# STM32F103RCT6_V2_1.net
KiCad netlist of a schematic drawn in Altium Designer
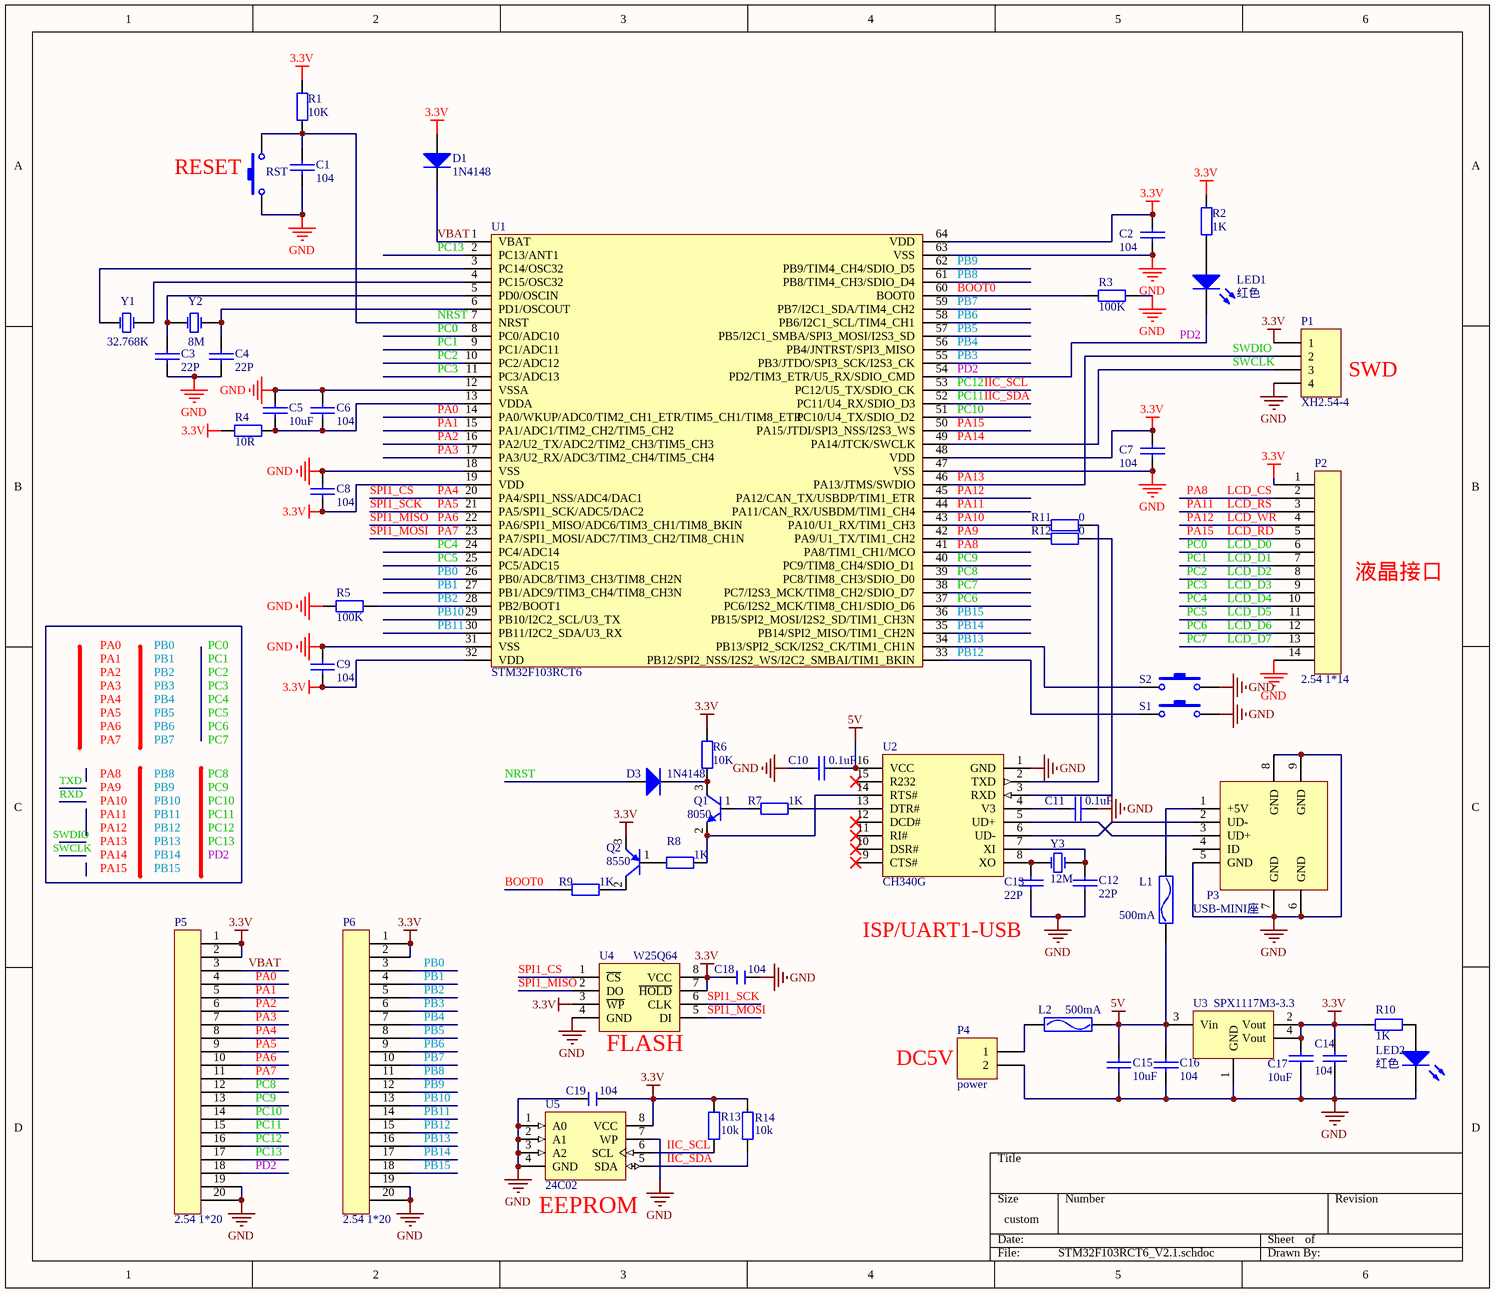
[diagram p0: STM32F103RCT6_V2.1.schdoc]

(export (version "E")
  (design (tool "Eeschema 10.0.6"))
  (components
    (comp (ref "C1") (value "104") (footprint "0805") (libsource (lib "Sch_Device__2010") (part "贴片电容 0805")))
    (comp (ref "C2") (value "104") (footprint "0805") (libsource (lib "Sch_Device__2010") (part "贴片电容 0805")))
    (comp (ref "C3") (value "22P") (footprint "0805") (libsource (lib "Sch_Device__2010") (part "贴片电容 0805")))
    (comp (ref "C4") (value "22P") (footprint "0805") (libsource (lib "Sch_Device__2010") (part "贴片电容 0805")))
    (comp (ref "C5")
      (value "10uF")
      (footprint "1206")
      (libsource (lib "Sch_Device__2010") (part "贴片电容 0805"))
    )
    (comp (ref "C6") (value "104") (footprint "0805") (libsource (lib "Sch_Device__2010") (part "贴片电容 0805")))
    (comp (ref "C7") (value "104") (footprint "0805") (libsource (lib "Sch_Device__2010") (part "贴片电容 0805")))
    (comp (ref "C8") (value "104") (footprint "0805") (libsource (lib "Sch_Device__2010") (part "贴片电容 0805")))
    (comp (ref "C9") (value "104") (footprint "0805") (libsource (lib "Sch_Device__2010") (part "贴片电容 0805")))
    (comp (ref "C10")
      (value "0.1uF")
      (footprint "0805")
      (libsource (lib "Sch_Device__2010") (part "贴片电容 0805"))
    )
    (comp (ref "C11")
      (value "0.1uF")
      (footprint "0805")
      (libsource (lib "Sch_Device__2010") (part "贴片电容 0805"))
    )
    (comp (ref "C12")
      (value "22P")
      (footprint "0805")
      (libsource (lib "Sch_Device__2010") (part "贴片电容 0805"))
    )
    (comp (ref "C13")
      (value "22P")
      (footprint "0805")
      (libsource (lib "Sch_Device__2010") (part "贴片电容 0805"))
    )
    (comp (ref "C14")
      (value "104")
      (footprint "0805")
      (libsource (lib "Sch_Device_Simple") (part "贴片电容 0805"))
    )
    (comp (ref "C15")
      (value "10uF")
      (footprint "1206")
      (libsource (lib "Sch_Device_Simple") (part "贴片电容 0805"))
    )
    (comp (ref "C16")
      (value "104")
      (footprint "0805")
      (libsource (lib "Sch_Device_Simple") (part "贴片电容 0805"))
    )
    (comp (ref "C17")
      (value "10uF")
      (footprint "1206")
      (libsource (lib "Sch_Device_Simple") (part "贴片电容 0805"))
    )
    (comp (ref "C18")
      (value "104")
      (footprint "0805")
      (description "无极性贴片电容")
      (fields (field (name "版权归属") "源创客"))
      (libsource (lib "STM32F407_CORE_BOARD") (part "C"))
    )
    (comp (ref "C19")
      (value "104")
      (footprint "0805")
      (description "无极性贴片电容")
      (fields (field (name "版权归属") "源创客"))
      (libsource (lib "STM32F407_CORE_BOARD") (part "C"))
    )
    (comp (ref "D1")
      (value "1N4148")
      (footprint "二极管 贴片 IN4148")
      (libsource (lib "Sch_Device_veryaz") (part "二极管 贴片 1N4148"))
    )
    (comp (ref "D3")
      (value "1N4148")
      (footprint "二极管 贴片 IN4148")
      (libsource (lib "") (part "二极管 贴片 1N4148_1"))
    )
    (comp (ref "L1") (value "500mA") (footprint "0805") (libsource (lib "Sch_Device_veryaz") (part "保险_自恢复")))
    (comp (ref "L2") (value "500mA") (footprint "0805") (libsource (lib "Sch_Device_veryaz") (part "保险_自恢复")))
    (comp (ref "LED1")
      (value "红色")
      (footprint "LED0805")
      (description "D_RED_D")
      (libsource (lib "Sch_Device_Simple") (part "发光二极管 Φ3"))
    )
    (comp (ref "LED2")
      (value "红色")
      (footprint "LED0805")
      (description "D_RED_D")
      (libsource (lib "Sch_Device_Simple") (part "发光二极管 Φ3"))
    )
    (comp (ref "P1")
      (value "XH2.54-4")
      (footprint "VH2.54_4")
      (libsource (lib "Sch_Device_veryaz") (part "联结件 XH2.54-4"))
    )
    (comp (ref "P2")
      (value "2.54 1*14")
      (footprint "单排插针 2.54 1*14")
      (libsource (lib "Sch_Device_veryaz") (part "联结件 单排插针 2.54 1*14"))
    )
    (comp (ref "P3")
      (value "USB-MINI座")
      (footprint "USB MINI DIP")
      (libsource (lib "Sch_Device_veryaz") (part "联结件 USB-MINI座"))
    )
    (comp (ref "P4")
      (value "power")
      (footprint "VH2.54_2")
      (libsource (lib "Sch_Device_Simple") (part "联结件 电源插头座"))
    )
    (comp (ref "P5")
      (value "2.54 1*20")
      (footprint "单排插针 2.54 1*20")
      (libsource (lib "Sch_Device_veryaz") (part "联结件 单排插针 2.54 1*20"))
    )
    (comp (ref "P6")
      (value "2.54 1*20")
      (footprint "单排插针 2.54 1*20")
      (libsource (lib "Sch_Device_veryaz") (part "联结件 单排插针 2.54 1*20"))
    )
    (comp (ref "Q1")
      (value "8050")
      (footprint "sot23b")
      (description "NPN 8050")
      (libsource (lib "Sch_Device_veryaz") (part "三极管 贴片 NPN"))
    )
    (comp (ref "Q2")
      (value "8550")
      (footprint "sot23b")
      (description "PNP 8550")
      (libsource (lib "Sch_Device_veryaz") (part "三极管 贴片PNP"))
    )
    (comp (ref "R1") (value "10K") (footprint "0805") (libsource (lib "") (part "贴片电阻 0603_2")))
    (comp (ref "R2") (value "1K") (footprint "0805") (libsource (lib "") (part "贴片电阻 0805_2")))
    (comp (ref "R3")
      (value "100K")
      (footprint "0805")
      (libsource (lib "Sch_Device_Simple") (part "贴片电阻 0805"))
    )
    (comp (ref "R4")
      (value "10R")
      (footprint "0805")
      (libsource (lib "Sch_Device_veryaz") (part "贴片电阻 0603"))
    )
    (comp (ref "R5") (value "100K") (footprint "0805") (libsource (lib "") (part "贴片电阻 0805_1")))
    (comp (ref "R6") (value "10K") (footprint "0805") (libsource (lib "") (part "贴片电阻 0603_1")))
    (comp (ref "R7") (value "1K") (footprint "0805") (libsource (lib "Sch_Device_veryaz") (part "贴片电阻 0603")))
    (comp (ref "R8") (value "1K") (footprint "0805") (libsource (lib "Sch_Device_veryaz") (part "贴片电阻 0603")))
    (comp (ref "R9") (value "1K") (footprint "0805") (libsource (lib "Sch_Device_veryaz") (part "贴片电阻 0603")))
    (comp (ref "R10")
      (value "1K")
      (footprint "0805")
      (libsource (lib "Sch_Device_Simple") (part "贴片电阻 0805"))
    )
    (comp (ref "R11") (value "0") (footprint "0805") (libsource (lib "Sch_Device_Simple") (part "贴片电阻 0805")))
    (comp (ref "R12") (value "0") (footprint "0805") (libsource (lib "Sch_Device_Simple") (part "贴片电阻 0805")))
    (comp (ref "R13")
      (value "10k")
      (footprint "0805")
      (description "贴片电阻")
      (fields (field (name "版权归属") "源创客"))
      (libsource (lib "STM32F407_CORE_BOARD") (part "R"))
    )
    (comp (ref "R14")
      (value "10k")
      (footprint "0805")
      (description "贴片电阻")
      (fields (field (name "版权归属") "源创客"))
      (libsource (lib "STM32F407_CORE_BOARD") (part "R"))
    )
    (comp (ref "RST") (value "key") (footprint "按键 轻触  6*3") (libsource (lib "") (part "按键 轻触 3*6_1")))
    (comp (ref "S1")
      (value "key")
      (footprint "按键 轻触  6*3")
      (libsource (lib "Sch_Device_veryaz") (part "按键 轻触 3*6"))
    )
    (comp (ref "S2")
      (value "key")
      (footprint "按键 轻触  6*3")
      (libsource (lib "Sch_Device_veryaz") (part "按键 轻触 3*6"))
    )
    (comp (ref "U1")
      (value "STM32F103RCT6")
      (footprint "Pcb Device_veryaz:LQFP64")
      (libsource (lib "Sch_Device_veryaz") (part "贴片芯片 STM32F103RCT6"))
    )
    (comp (ref "U2")
      (value "CH340G")
      (footprint "SOIC16")
      (libsource (lib "Sch_Device_veryaz") (part "贴片芯片 CH340G"))
    )
    (comp (ref "U3")
      (value "SPX1117M3-3.3")
      (footprint "SOT223")
      (libsource (lib "Sch_Device_veryaz") (part "贴片芯片 SPX1117M3-5.0"))
    )
    (comp (ref "U4")
      (value "W25Q64")
      (footprint "SO8-W")
      (description "外置Flash")
      (fields (field (name "版权归属") "源创客"))
      (libsource (lib "STM32F407_CORE_BOARD") (part "W25Qxx"))
    )
    (comp (ref "U5")
      (value "24C02")
      (footprint "SOIC8")
      (description "外置EEPROM")
      (fields (field (name "版权归属") "源创客"))
      (libsource (lib "STM32F407_CORE_BOARD") (part "24Cxx"))
    )
    (comp (ref "Y1")
      (value "32.768K")
      (footprint "晶振 卧 BCY-W2/D3.1")
      (libsource (lib "Sch_Device_veryaz") (part "晶振 直插矮"))
    )
    (comp (ref "Y2")
      (value "8M")
      (footprint "晶振 BCY-W2/E4.7")
      (libsource (lib "Sch_Device_veryaz") (part "晶振 直插矮"))
    )
    (comp (ref "Y3")
      (value "12M")
      (footprint "晶振 BCY-W2/E4.7")
      (libsource (lib "Sch_Device_veryaz") (part "晶振 直插矮"))
    )
  )
  (nets
    (net (code "1") (name "/BOOT0") (class "Default")
      (node (ref "R3") (pin "2") (pinfunction "2_2") (pintype "passive"))
      (node (ref "R9") (pin "1") (pinfunction "1_1") (pintype "passive"))
      (node (ref "U1") (pin "60") (pinfunction "BOOT0_60") (pintype "passive"))
    )
    (net (code "2") (name "/IIC_SCL") (class "Default")
      (node (ref "P5") (pin "16") (pinfunction "16_16") (pintype "passive"))
      (node (ref "R13") (pin "2") (pinfunction "2_2") (pintype "passive"))
      (node (ref "U1") (pin "53") (pinfunction "PC12/U5_TX/SDIO_CK_53") (pintype "passive"))
      (node (ref "U5") (pin "6") (pinfunction "SCL_6") (pintype "input"))
    )
    (net (code "3") (name "/IIC_SDA") (class "Default")
      (node (ref "P5") (pin "15") (pinfunction "15_15") (pintype "passive"))
      (node (ref "R14") (pin "2") (pinfunction "2_2") (pintype "passive"))
      (node (ref "U1") (pin "52") (pinfunction "PC11/U4_RX/SDIO_D3_52") (pintype "passive"))
      (node (ref "U5") (pin "5") (pinfunction "SDA_5") (pintype "bidirectional"))
    )
    (net (code "4") (name "/LCD_CS") (class "Default")
      (node (ref "P2") (pin "2") (pinfunction "2_2") (pintype "passive"))
      (node (ref "U1") (pin "41") (pinfunction "PA8/TIM1_CH1/MCO_41") (pintype "passive"))
    )
    (net (code "5") (name "/LCD_D0") (class "Default")
      (node (ref "P2") (pin "6") (pinfunction "6_6") (pintype "passive"))
      (node (ref "U1") (pin "8") (pinfunction "PC0/ADC10_8") (pintype "passive"))
    )
    (net (code "6") (name "/LCD_D1") (class "Default")
      (node (ref "P2") (pin "7") (pinfunction "7_7") (pintype "passive"))
      (node (ref "U1") (pin "9") (pinfunction "PC1/ADC11_9") (pintype "passive"))
    )
    (net (code "7") (name "/LCD_D2") (class "Default")
      (node (ref "P2") (pin "8") (pinfunction "8_8") (pintype "passive"))
      (node (ref "U1") (pin "10") (pinfunction "PC2/ADC12_10") (pintype "passive"))
    )
    (net (code "8") (name "/LCD_D3") (class "Default")
      (node (ref "P2") (pin "9") (pinfunction "9_9") (pintype "passive"))
      (node (ref "U1") (pin "11") (pinfunction "PC3/ADC13_11") (pintype "passive"))
    )
    (net (code "9") (name "/LCD_D4") (class "Default")
      (node (ref "P2") (pin "10") (pinfunction "10_10") (pintype "passive"))
      (node (ref "U1") (pin "24") (pinfunction "PC4/ADC14_24") (pintype "passive"))
    )
    (net (code "10") (name "/LCD_D5") (class "Default")
      (node (ref "P2") (pin "11") (pinfunction "11_11") (pintype "passive"))
      (node (ref "U1") (pin "25") (pinfunction "PC5/ADC15_25") (pintype "passive"))
    )
    (net (code "11") (name "/LCD_D6") (class "Default")
      (node (ref "P2") (pin "12") (pinfunction "12_12") (pintype "passive"))
      (node (ref "U1") (pin "37") (pinfunction "PC6/I2S2_MCK/TIM8_CH1/SDIO_D6_37") (pintype "passive"))
    )
    (net (code "12") (name "/LCD_D7") (class "Default")
      (node (ref "P2") (pin "13") (pinfunction "13_13") (pintype "passive"))
      (node (ref "U1") (pin "38") (pinfunction "PC7/I2S3_MCK/TIM8_CH2/SDIO_D7_38") (pintype "passive"))
    )
    (net (code "13") (name "/LCD_RD") (class "Default")
      (node (ref "P2") (pin "5") (pinfunction "5_5") (pintype "passive"))
      (node (ref "U1") (pin "50") (pinfunction "PA15/JTDI/SPI3_NSS/I2S3_WS_50") (pintype "passive"))
    )
    (net (code "14") (name "/LCD_RS") (class "Default")
      (node (ref "P2") (pin "3") (pinfunction "3_3") (pintype "passive"))
      (node (ref "U1") (pin "44") (pinfunction "PA11/CAN_RX/USBDM/TIM1_CH4_44") (pintype "passive"))
    )
    (net (code "15") (name "/LCD_WR") (class "Default")
      (node (ref "P2") (pin "4") (pinfunction "4_4") (pintype "passive"))
      (node (ref "U1") (pin "45") (pinfunction "PA12/CAN_TX/USBDP/TIM1_ETR_45") (pintype "passive"))
    )
    (net (code "16") (name "/NRST") (class "Default")
      (node (ref "C1") (pin "2") (pintype "passive"))
      (node (ref "D3") (pin "1") (pinfunction "A_1") (pintype "passive"))
      (node (ref "R1") (pin "2") (pinfunction "2_2") (pintype "passive"))
      (node (ref "RST") (pin "2") (pinfunction "2_2") (pintype "passive"))
      (node (ref "U1") (pin "7") (pinfunction "NRST_7") (pintype "passive"))
    )
    (net (code "17") (name "/PA0") (class "Default")
      (node (ref "P5") (pin "4") (pinfunction "4_4") (pintype "passive"))
      (node (ref "U1") (pin "14") (pinfunction "PA0/WKUP/ADC0/TIM2_CH1_ETR/TIM5_CH1/TIM8_ETR_14") (pintype "passive"))
    )
    (net (code "18") (name "/PA1") (class "Default")
      (node (ref "P5") (pin "5") (pinfunction "5_5") (pintype "passive"))
      (node (ref "U1") (pin "15") (pinfunction "PA1/ADC1/TIM2_CH2/TIM5_CH2_15") (pintype "passive"))
    )
    (net (code "19") (name "/PA2") (class "Default")
      (node (ref "P5") (pin "6") (pinfunction "6_6") (pintype "passive"))
      (node (ref "U1") (pin "16") (pinfunction "PA2/U2_TX/ADC2/TIM2_CH3/TIM5_CH3_16") (pintype "passive"))
    )
    (net (code "20") (name "/PA3") (class "Default")
      (node (ref "P5") (pin "7") (pinfunction "7_7") (pintype "passive"))
      (node (ref "U1") (pin "17") (pinfunction "PA3/U2_RX/ADC3/TIM2_CH4/TIM5_CH4_17") (pintype "passive"))
    )
    (net (code "21") (name "/PA4") (class "Default")
      (node (ref "P5") (pin "8") (pinfunction "8_8") (pintype "passive"))
      (node (ref "U1") (pin "20") (pinfunction "PA4/SPI1_NSS/ADC4/DAC1_20") (pintype "passive"))
      (node (ref "U4") (pin "1") (pinfunction "~{CS}_1") (pintype "passive"))
    )
    (net (code "22") (name "/PA5") (class "Default")
      (node (ref "P5") (pin "9") (pinfunction "9_9") (pintype "passive"))
      (node (ref "U1") (pin "21") (pinfunction "PA5/SPI1_SCK/ADC5/DAC2_21") (pintype "passive"))
      (node (ref "U4") (pin "6") (pinfunction "CLK_6") (pintype "passive"))
    )
    (net (code "23") (name "/PA6") (class "Default")
      (node (ref "P5") (pin "10") (pinfunction "10_10") (pintype "passive"))
      (node (ref "U1") (pin "22") (pinfunction "PA6/SPI1_MISO/ADC6/TIM3_CH1/TIM8_BKIN_22") (pintype "passive"))
      (node (ref "U4") (pin "2") (pinfunction "DO_2") (pintype "passive"))
    )
    (net (code "24") (name "/PA7") (class "Default")
      (node (ref "P5") (pin "11") (pinfunction "11_11") (pintype "passive"))
      (node (ref "U1") (pin "23") (pinfunction "PA7/SPI1_MOSI/ADC7/TIM3_CH2/TIM8_CH1N_23") (pintype "passive"))
      (node (ref "U4") (pin "5") (pinfunction "DI_5") (pintype "passive"))
    )
    (net (code "25") (name "/PA9") (class "Default")
      (node (ref "R12") (pin "2") (pinfunction "2_2") (pintype "passive"))
      (node (ref "U1") (pin "42") (pinfunction "PA9/U1_TX/TIM1_CH2_42") (pintype "passive"))
    )
    (net (code "26") (name "/PA10") (class "Default")
      (node (ref "R11") (pin "2") (pinfunction "2_2") (pintype "passive"))
      (node (ref "U1") (pin "43") (pinfunction "PA10/U1_RX/TIM1_CH3_43") (pintype "passive"))
    )
    (net (code "27") (name "/PA13") (class "Default")
      (node (ref "P1") (pin "2") (pinfunction "2_2") (pintype "passive"))
      (node (ref "U1") (pin "46") (pinfunction "PA13/JTMS/SWDIO_46") (pintype "passive"))
    )
    (net (code "28") (name "/PA14") (class "Default")
      (node (ref "P1") (pin "3") (pinfunction "3_3") (pintype "passive"))
      (node (ref "U1") (pin "49") (pinfunction "PA14/JTCK/SWCLK_49") (pintype "passive"))
    )
    (net (code "29") (name "/PB0") (class "Default")
      (node (ref "P6") (pin "3") (pinfunction "3_3") (pintype "passive"))
      (node (ref "U1") (pin "26") (pinfunction "PB0/ADC8/TIM3_CH3/TIM8_CH2N_26") (pintype "passive"))
    )
    (net (code "30") (name "/PB1") (class "Default")
      (node (ref "P6") (pin "4") (pinfunction "4_4") (pintype "passive"))
      (node (ref "U1") (pin "27") (pinfunction "PB1/ADC9/TIM3_CH4/TIM8_CH3N_27") (pintype "passive"))
    )
    (net (code "31") (name "/PB2") (class "Default")
      (node (ref "P6") (pin "5") (pinfunction "5_5") (pintype "passive"))
      (node (ref "R5") (pin "2") (pinfunction "2_2") (pintype "passive"))
      (node (ref "U1") (pin "28") (pinfunction "PB2/BOOT1_28") (pintype "passive"))
    )
    (net (code "32") (name "/PB3") (class "Default")
      (node (ref "P6") (pin "6") (pinfunction "6_6") (pintype "passive"))
      (node (ref "U1") (pin "55") (pinfunction "PB3/JTDO/SPI3_SCK/I2S3_CK_55") (pintype "passive"))
    )
    (net (code "33") (name "/PB4") (class "Default")
      (node (ref "P6") (pin "7") (pinfunction "7_7") (pintype "passive"))
      (node (ref "U1") (pin "56") (pinfunction "PB4/JNTRST/SPI3_MISO_56") (pintype "passive"))
    )
    (net (code "34") (name "/PB5") (class "Default")
      (node (ref "P6") (pin "8") (pinfunction "8_8") (pintype "passive"))
      (node (ref "U1") (pin "57") (pinfunction "PB5/I2C1_SMBA/SPI3_MOSI/I2S3_SD_57") (pintype "passive"))
    )
    (net (code "35") (name "/PB6") (class "Default")
      (node (ref "P6") (pin "9") (pinfunction "9_9") (pintype "passive"))
      (node (ref "U1") (pin "58") (pinfunction "PB6/I2C1_SCL/TIM4_CH1_58") (pintype "passive"))
    )
    (net (code "36") (name "/PB7") (class "Default")
      (node (ref "P6") (pin "10") (pinfunction "10_10") (pintype "passive"))
      (node (ref "U1") (pin "59") (pinfunction "PB7/I2C1_SDA/TIM4_CH2_59") (pintype "passive"))
    )
    (net (code "37") (name "/PB8") (class "Default")
      (node (ref "P6") (pin "11") (pinfunction "11_11") (pintype "passive"))
      (node (ref "U1") (pin "61") (pinfunction "PB8/TIM4_CH3/SDIO_D4_61") (pintype "passive"))
    )
    (net (code "38") (name "/PB9") (class "Default")
      (node (ref "P6") (pin "12") (pinfunction "12_12") (pintype "passive"))
      (node (ref "U1") (pin "62") (pinfunction "PB9/TIM4_CH4/SDIO_D5_62") (pintype "passive"))
    )
    (net (code "39") (name "/PB10") (class "Default")
      (node (ref "P6") (pin "13") (pinfunction "13_13") (pintype "passive"))
      (node (ref "U1") (pin "29") (pinfunction "PB10/I2C2_SCL/U3_TX_29") (pintype "passive"))
    )
    (net (code "40") (name "/PB11") (class "Default")
      (node (ref "P6") (pin "14") (pinfunction "14_14") (pintype "passive"))
      (node (ref "U1") (pin "30") (pinfunction "PB11/I2C2_SDA/U3_RX_30") (pintype "passive"))
    )
    (net (code "41") (name "/PB12") (class "Default")
      (node (ref "P6") (pin "15") (pinfunction "15_15") (pintype "passive"))
      (node (ref "S1") (pin "2") (pinfunction "2_2") (pintype "passive"))
      (node (ref "U1") (pin "33") (pinfunction "PB12/SPI2_NSS/I2S2_WS/I2C2_SMBAI/TIM1_BKIN_33") (pintype "passive"))
    )
    (net (code "42") (name "/PB13") (class "Default")
      (node (ref "P6") (pin "16") (pinfunction "16_16") (pintype "passive"))
      (node (ref "S2") (pin "2") (pinfunction "2_2") (pintype "passive"))
      (node (ref "U1") (pin "34") (pinfunction "PB13/SPI2_SCK/I2S2_CK/TIM1_CH1N_34") (pintype "passive"))
    )
    (net (code "43") (name "/PB14") (class "Default")
      (node (ref "P6") (pin "17") (pinfunction "17_17") (pintype "passive"))
      (node (ref "U1") (pin "35") (pinfunction "PB14/SPI2_MISO/TIM1_CH2N_35") (pintype "passive"))
    )
    (net (code "44") (name "/PB15") (class "Default")
      (node (ref "P6") (pin "18") (pinfunction "18_18") (pintype "passive"))
      (node (ref "U1") (pin "36") (pinfunction "PB15/SPI2_MOSI/I2S2_SD/TIM1_CH3N_36") (pintype "passive"))
    )
    (net (code "45") (name "/PC8") (class "Default")
      (node (ref "P5") (pin "12") (pinfunction "12_12") (pintype "passive"))
      (node (ref "U1") (pin "39") (pinfunction "PC8/TIM8_CH3/SDIO_D0_39") (pintype "passive"))
    )
    (net (code "46") (name "/PC9") (class "Default")
      (node (ref "P5") (pin "13") (pinfunction "13_13") (pintype "passive"))
      (node (ref "U1") (pin "40") (pinfunction "PC9/TIM8_CH4/SDIO_D1_40") (pintype "passive"))
    )
    (net (code "47") (name "/PC10") (class "Default")
      (node (ref "P5") (pin "14") (pinfunction "14_14") (pintype "passive"))
      (node (ref "U1") (pin "51") (pinfunction "PC10/U4_TX/SDIO_D2_51") (pintype "passive"))
    )
    (net (code "48") (name "/PC13") (class "Default")
      (node (ref "P5") (pin "17") (pinfunction "17_17") (pintype "passive"))
      (node (ref "U1") (pin "2") (pinfunction "PC13/ANT1_2") (pintype "passive"))
    )
    (net (code "49") (name "/PD2") (class "Default")
      (node (ref "LED1") (pin "2") (pinfunction "K_2") (pintype "passive"))
      (node (ref "P5") (pin "18") (pinfunction "18_18") (pintype "passive"))
      (node (ref "U1") (pin "54") (pinfunction "PD2/TIM3_ETR/U5_RX/SDIO_CMD_54") (pintype "passive"))
    )
    (net (code "50") (name "/VBAT") (class "Default")
      (node (ref "D1") (pin "2") (pinfunction "K_2") (pintype "passive"))
      (node (ref "P5") (pin "3") (pinfunction "3_3") (pintype "passive"))
      (node (ref "U1") (pin "1") (pinfunction "VBAT_1") (pintype "passive"))
    )
    (net (code "51") (name "3.3V") (class "Default")
      (node (ref "C14") (pin "1") (pintype "passive"))
      (node (ref "C17") (pin "1") (pintype "passive"))
      (node (ref "C18") (pin "2") (pinfunction "2_2") (pintype "passive"))
      (node (ref "C19") (pin "1") (pinfunction "1_1") (pintype "passive"))
      (node (ref "C2") (pin "1") (pintype "passive"))
      (node (ref "C7") (pin "1") (pintype "passive"))
      (node (ref "C8") (pin "1") (pintype "passive"))
      (node (ref "C9") (pin "1") (pintype "passive"))
      (node (ref "D1") (pin "1") (pinfunction "A_1") (pintype "passive"))
      (node (ref "P1") (pin "1") (pinfunction "1_1") (pintype "passive"))
      (node (ref "P2") (pin "1") (pinfunction "1_1") (pintype "passive"))
      (node (ref "P5") (pin "1") (pinfunction "1_1") (pintype "passive"))
      (node (ref "P5") (pin "2") (pinfunction "2_2") (pintype "passive"))
      (node (ref "P6") (pin "1") (pinfunction "1_1") (pintype "passive"))
      (node (ref "P6") (pin "2") (pinfunction "2_2") (pintype "passive"))
      (node (ref "Q2") (pin "3") (pinfunction "E_3") (pintype "passive"))
      (node (ref "R1") (pin "1") (pinfunction "1_1") (pintype "passive"))
      (node (ref "R10") (pin "2") (pinfunction "2_2") (pintype "passive"))
      (node (ref "R13") (pin "1") (pinfunction "1_1") (pintype "passive"))
      (node (ref "R14") (pin "1") (pinfunction "1_1") (pintype "passive"))
      (node (ref "R2") (pin "1") (pinfunction "1_1") (pintype "passive"))
      (node (ref "R4") (pin "1") (pinfunction "1_1") (pintype "passive"))
      (node (ref "R6") (pin "2") (pinfunction "2_2") (pintype "passive"))
      (node (ref "U1") (pin "19") (pinfunction "VDD_19") (pintype "passive"))
      (node (ref "U1") (pin "32") (pinfunction "VDD_32") (pintype "passive"))
      (node (ref "U1") (pin "48") (pinfunction "VDD_48") (pintype "passive"))
      (node (ref "U1") (pin "64") (pinfunction "VDD_64") (pintype "passive"))
      (node (ref "U3") (pin "2") (pinfunction "Vout_2") (pintype "passive"))
      (node (ref "U3") (pin "4") (pinfunction "Vout_4") (pintype "passive"))
      (node (ref "U4") (pin "3") (pinfunction "~{WP}_3") (pintype "passive"))
      (node (ref "U4") (pin "7") (pinfunction "~{HOLD}_7") (pintype "passive"))
      (node (ref "U4") (pin "8") (pinfunction "VCC_8") (pintype "passive"))
      (node (ref "U5") (pin "8") (pinfunction "VCC_8") (pintype "power_in"))
    )
    (net (code "52") (name "5V") (class "Default")
      (node (ref "C10") (pin "1") (pintype "passive"))
      (node (ref "C15") (pin "1") (pintype "passive"))
      (node (ref "C16") (pin "1") (pintype "passive"))
      (node (ref "L1") (pin "1") (pinfunction "1_1") (pintype "passive"))
      (node (ref "L2") (pin "1") (pinfunction "1_1") (pintype "passive"))
      (node (ref "U2") (pin "16") (pinfunction "VCC_16") (pintype "passive"))
      (node (ref "U3") (pin "3") (pinfunction "Vin_3") (pintype "passive"))
    )
    (net (code "53") (name "GND") (class "Default")
      (node (ref "C1") (pin "1") (pintype "passive"))
      (node (ref "C10") (pin "2") (pintype "passive"))
      (node (ref "C11") (pin "1") (pintype "passive"))
      (node (ref "C12") (pin "1") (pintype "passive"))
      (node (ref "C13") (pin "1") (pintype "passive"))
      (node (ref "C14") (pin "2") (pintype "passive"))
      (node (ref "C15") (pin "2") (pintype "passive"))
      (node (ref "C16") (pin "2") (pintype "passive"))
      (node (ref "C17") (pin "2") (pintype "passive"))
      (node (ref "C18") (pin "1") (pinfunction "1_1") (pintype "passive"))
      (node (ref "C19") (pin "2") (pinfunction "2_2") (pintype "passive"))
      (node (ref "C2") (pin "2") (pintype "passive"))
      (node (ref "C3") (pin "1") (pintype "passive"))
      (node (ref "C4") (pin "1") (pintype "passive"))
      (node (ref "C5") (pin "2") (pintype "passive"))
      (node (ref "C6") (pin "2") (pintype "passive"))
      (node (ref "C7") (pin "2") (pintype "passive"))
      (node (ref "C8") (pin "2") (pintype "passive"))
      (node (ref "C9") (pin "2") (pintype "passive"))
      (node (ref "LED2") (pin "2") (pinfunction "K_2") (pintype "passive"))
      (node (ref "P1") (pin "4") (pinfunction "4_4") (pintype "passive"))
      (node (ref "P2") (pin "14") (pinfunction "14_14") (pintype "passive"))
      (node (ref "P3") (pin "5") (pinfunction "GND_5") (pintype "passive"))
      (node (ref "P3") (pin "6") (pinfunction "GND_6") (pintype "passive"))
      (node (ref "P3") (pin "7") (pinfunction "GND_7") (pintype "passive"))
      (node (ref "P3") (pin "8") (pinfunction "GND_8") (pintype "passive"))
      (node (ref "P3") (pin "9") (pinfunction "GND_9") (pintype "passive"))
      (node (ref "P4") (pin "2") (pinfunction "2_2") (pintype "passive"))
      (node (ref "P5") (pin "19") (pinfunction "19_19") (pintype "passive"))
      (node (ref "P5") (pin "20") (pinfunction "20_20") (pintype "passive"))
      (node (ref "P6") (pin "19") (pinfunction "19_19") (pintype "passive"))
      (node (ref "P6") (pin "20") (pinfunction "20_20") (pintype "passive"))
      (node (ref "R3") (pin "1") (pinfunction "1_1") (pintype "passive"))
      (node (ref "R5") (pin "1") (pinfunction "1_1") (pintype "passive"))
      (node (ref "RST") (pin "1") (pinfunction "1_1") (pintype "passive"))
      (node (ref "S1") (pin "1") (pinfunction "1_1") (pintype "passive"))
      (node (ref "S2") (pin "1") (pinfunction "1_1") (pintype "passive"))
      (node (ref "U1") (pin "12") (pinfunction "VSSA_12") (pintype "passive"))
      (node (ref "U1") (pin "18") (pinfunction "VSS_18") (pintype "passive"))
      (node (ref "U1") (pin "31") (pinfunction "VSS_31") (pintype "passive"))
      (node (ref "U1") (pin "47") (pinfunction "VSS_47") (pintype "passive"))
      (node (ref "U1") (pin "63") (pinfunction "VSS_63") (pintype "passive"))
      (node (ref "U2") (pin "1") (pinfunction "GND_1") (pintype "passive"))
      (node (ref "U3") (pin "1") (pinfunction "GND_1") (pintype "passive"))
      (node (ref "U4") (pin "4") (pinfunction "GND_4") (pintype "passive"))
      (node (ref "U5") (pin "1") (pinfunction "A0_1") (pintype "input"))
      (node (ref "U5") (pin "2") (pinfunction "A1_2") (pintype "input"))
      (node (ref "U5") (pin "3") (pinfunction "A2_3") (pintype "input"))
      (node (ref "U5") (pin "4") (pinfunction "GND_4") (pintype "passive"))
      (node (ref "U5") (pin "7") (pinfunction "WP_7") (pintype "passive"))
    )
    (net (code "54") (name "Net-(D3-K)") (class "Default")
      (node (ref "D3") (pin "2") (pinfunction "K_2") (pintype "passive"))
      (node (ref "Q1") (pin "3") (pinfunction "C_3") (pintype "passive"))
      (node (ref "R6") (pin "1") (pinfunction "1_1") (pintype "passive"))
    )
    (net (code "55") (name "Net-(L2-Pad2)") (class "Default")
      (node (ref "L2") (pin "2") (pinfunction "2_2") (pintype "passive"))
      (node (ref "P4") (pin "1") (pinfunction "1_1") (pintype "passive"))
    )
    (net (code "56") (name "Net-(LED1-A)") (class "Default")
      (node (ref "LED1") (pin "1") (pinfunction "A_1") (pintype "passive"))
      (node (ref "R2") (pin "2") (pinfunction "2_2") (pintype "passive"))
    )
    (net (code "57") (name "Net-(LED2-A)") (class "Default")
      (node (ref "LED2") (pin "1") (pinfunction "A_1") (pintype "passive"))
      (node (ref "R10") (pin "1") (pinfunction "1_1") (pintype "passive"))
    )
    (net (code "58") (name "Net-(P3-+5V)") (class "Default")
      (node (ref "L1") (pin "2") (pinfunction "2_2") (pintype "passive"))
      (node (ref "P3") (pin "1") (pinfunction "+5V_1") (pintype "passive"))
    )
    (net (code "59") (name "Net-(P3-UD+)") (class "Default")
      (node (ref "P3") (pin "3") (pinfunction "UD+_3") (pintype "passive"))
      (node (ref "U2") (pin "5") (pinfunction "UD+_5") (pintype "passive"))
    )
    (net (code "60") (name "Net-(P3-UD-)") (class "Default")
      (node (ref "P3") (pin "2") (pinfunction "UD-_2") (pintype "passive"))
      (node (ref "U2") (pin "6") (pinfunction "UD-_6") (pintype "passive"))
    )
    (net (code "61") (name "Net-(Q1-B)") (class "Default")
      (node (ref "Q1") (pin "1") (pinfunction "B_1") (pintype "passive"))
      (node (ref "R7") (pin "1") (pinfunction "1_1") (pintype "passive"))
    )
    (net (code "62") (name "Net-(Q1-E)") (class "Default")
      (node (ref "Q1") (pin "2") (pinfunction "E_2") (pintype "passive"))
      (node (ref "R8") (pin "2") (pinfunction "2_2") (pintype "passive"))
      (node (ref "U2") (pin "14") (pinfunction "RTS#_14") (pintype "passive"))
    )
    (net (code "63") (name "Net-(Q2-B)") (class "Default")
      (node (ref "Q2") (pin "1") (pinfunction "B_1") (pintype "passive"))
      (node (ref "R8") (pin "1") (pinfunction "1_1") (pintype "passive"))
    )
    (net (code "64") (name "Net-(Q2-C)") (class "Default")
      (node (ref "Q2") (pin "2") (pinfunction "C_2") (pintype "passive"))
      (node (ref "R9") (pin "2") (pinfunction "2_2") (pintype "passive"))
    )
    (net (code "65") (name "Net-(U1-PC14{slash}OSC32)") (class "Default")
      (node (ref "U1") (pin "3") (pinfunction "PC14/OSC32_3") (pintype "passive"))
      (node (ref "Y1") (pin "1") (pinfunction "OSC1_1") (pintype "passive"))
    )
    (net (code "66") (name "Net-(U1-PC15{slash}OSC32)") (class "Default")
      (node (ref "U1") (pin "4") (pinfunction "PC15/OSC32_4") (pintype "passive"))
      (node (ref "Y1") (pin "2") (pinfunction "OSC2_2") (pintype "passive"))
    )
    (net (code "67") (name "Net-(U1-PD0{slash}OSCIN)") (class "Default")
      (node (ref "C3") (pin "2") (pintype "passive"))
      (node (ref "U1") (pin "5") (pinfunction "PD0/OSCIN_5") (pintype "passive"))
      (node (ref "Y2") (pin "2") (pinfunction "OSC2_2") (pintype "passive"))
    )
    (net (code "68") (name "Net-(U1-PD1{slash}OSCOUT)") (class "Default")
      (node (ref "C4") (pin "2") (pintype "passive"))
      (node (ref "U1") (pin "6") (pinfunction "PD1/OSCOUT_6") (pintype "passive"))
      (node (ref "Y2") (pin "1") (pinfunction "OSC1_1") (pintype "passive"))
    )
    (net (code "69") (name "Net-(U1-VDDA)") (class "Default")
      (node (ref "C5") (pin "1") (pintype "passive"))
      (node (ref "C6") (pin "1") (pintype "passive"))
      (node (ref "R4") (pin "2") (pinfunction "2_2") (pintype "passive"))
      (node (ref "U1") (pin "13") (pinfunction "VDDA_13") (pintype "passive"))
    )
    (net (code "70") (name "Net-(U2-DTR#)") (class "Default")
      (node (ref "R7") (pin "2") (pinfunction "2_2") (pintype "passive"))
      (node (ref "U2") (pin "13") (pinfunction "DTR#_13") (pintype "passive"))
    )
    (net (code "71") (name "Net-(U2-RXD)") (class "Default")
      (node (ref "R12") (pin "1") (pinfunction "1_1") (pintype "passive"))
      (node (ref "U2") (pin "3") (pinfunction "RXD_3") (pintype "input"))
    )
    (net (code "72") (name "Net-(U2-TXD)") (class "Default")
      (node (ref "R11") (pin "1") (pinfunction "1_1") (pintype "passive"))
      (node (ref "U2") (pin "2") (pinfunction "TXD_2") (pintype "output"))
    )
    (net (code "73") (name "Net-(U2-V3)") (class "Default")
      (node (ref "C11") (pin "2") (pintype "passive"))
      (node (ref "U2") (pin "4") (pinfunction "V3_4") (pintype "passive"))
    )
    (net (code "74") (name "Net-(U2-XI)") (class "Default")
      (node (ref "C12") (pin "2") (pintype "passive"))
      (node (ref "U2") (pin "7") (pinfunction "XI_7") (pintype "passive"))
      (node (ref "Y3") (pin "1") (pinfunction "OSC1_1") (pintype "passive"))
    )
    (net (code "75") (name "Net-(U2-XO)") (class "Default")
      (node (ref "C13") (pin "2") (pintype "passive"))
      (node (ref "U2") (pin "8") (pinfunction "XO_8") (pintype "passive"))
      (node (ref "Y3") (pin "2") (pinfunction "OSC2_2") (pintype "passive"))
    )
    (net (code "76") (name "unconnected-(P3-ID-Pad4)") (class "Default")
      (node (ref "P3") (pin "4") (pinfunction "ID_4") (pintype "passive"))
    )
    (net (code "77") (name "unconnected-(U2-CTS#-Pad9)") (class "Default")
      (node (ref "U2") (pin "9") (pinfunction "CTS#_9") (pintype "passive+no_connect"))
    )
    (net (code "78") (name "unconnected-(U2-DCD#-Pad12)") (class "Default")
      (node (ref "U2") (pin "12") (pinfunction "DCD#_12") (pintype "passive+no_connect"))
    )
    (net (code "79") (name "unconnected-(U2-DSR#-Pad10)") (class "Default")
      (node (ref "U2") (pin "10") (pinfunction "DSR#_10") (pintype "passive+no_connect"))
    )
    (net (code "80") (name "unconnected-(U2-R232-Pad15)") (class "Default")
      (node (ref "U2") (pin "15") (pinfunction "R232_15") (pintype "passive+no_connect"))
    )
    (net (code "81") (name "unconnected-(U2-RI#-Pad11)") (class "Default")
      (node (ref "U2") (pin "11") (pinfunction "RI#_11") (pintype "passive+no_connect"))
    )
  )
)
